# CIRCUIT_SCHEMATIC.net
KiCad netlist of a schematic drawn in EAGLE
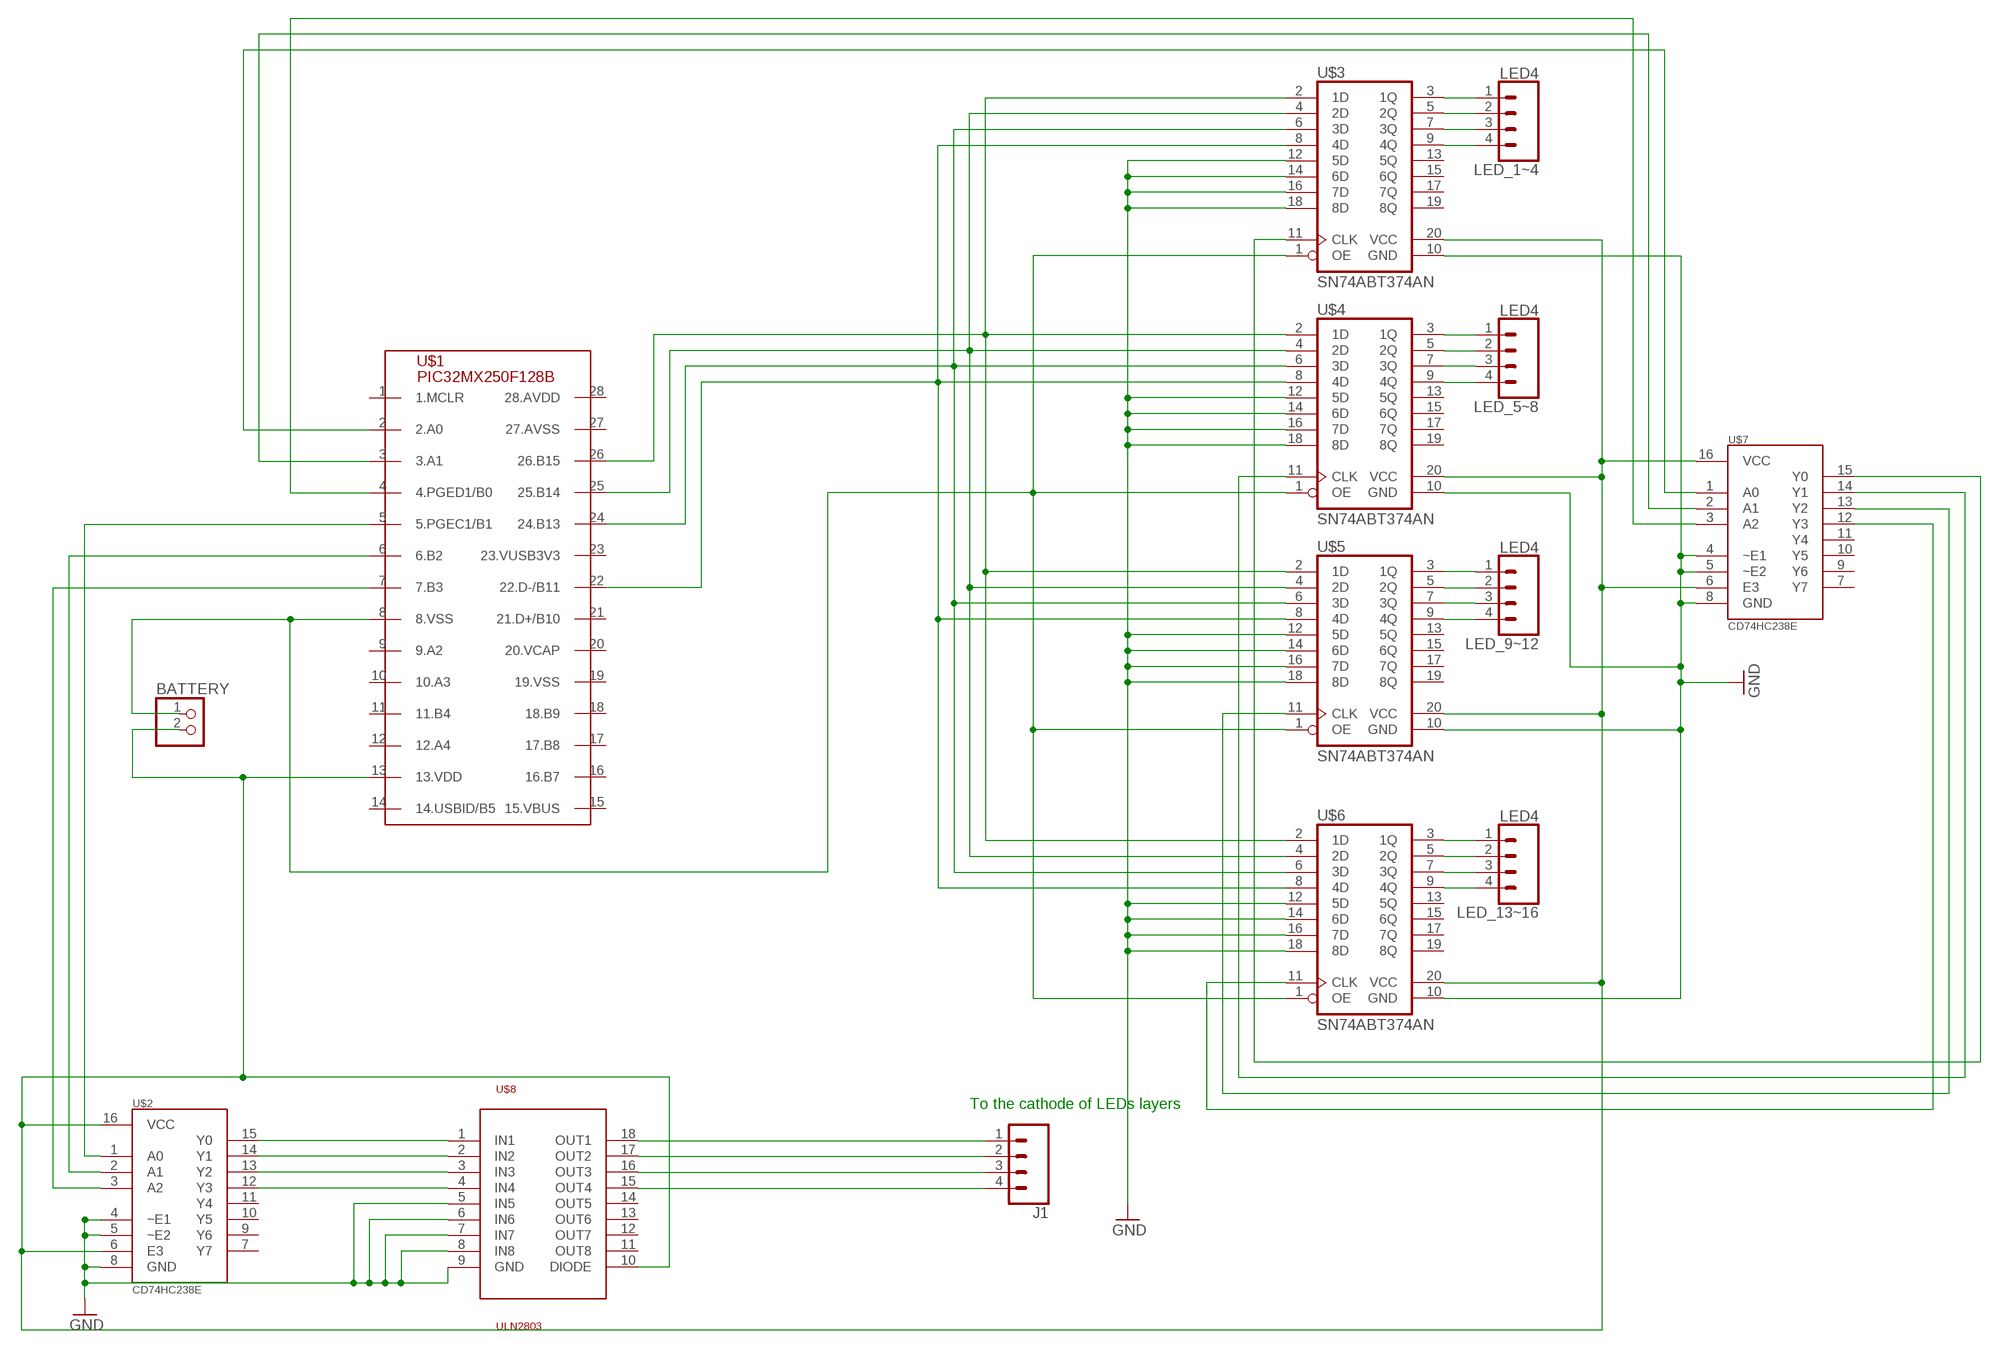
[diagram p0: schematic, sheet 1]

(export (version "E")
  (design (tool "Eeschema 10.0.6"))
  (components
    (comp (ref "BATTERY")
      (value "PINHD-1X2")
      (footprint "eagle-import:1X02")
      (libsource (lib "eagle-import") (part "PINHD-1X2"))
    )
    (comp (ref "J1")
      (value "CONN_04")
      (footprint "eagle-import:1X04")
      (libsource (lib "eagle-import") (part "CONN_04"))
    )
    (comp (ref "LED_1~4")
      (value "LED4")
      (footprint "eagle-import:1X04")
      (libsource (lib "eagle-import") (part "LED4"))
    )
    (comp (ref "LED_5~8")
      (value "LED4")
      (footprint "eagle-import:1X04")
      (libsource (lib "eagle-import") (part "LED4"))
    )
    (comp (ref "LED_9~12")
      (value "LED4")
      (footprint "eagle-import:1X04")
      (libsource (lib "eagle-import") (part "LED4"))
    )
    (comp (ref "LED_13~16")
      (value "LED4")
      (footprint "eagle-import:1X04")
      (libsource (lib "eagle-import") (part "LED4"))
    )
    (comp (ref "U$1")
      (value "PIC32MX250F128B")
      (footprint "eagle-import:DIL28-3")
      (libsource (lib "eagle-import") (part "PIC32MX250F128B"))
    )
    (comp (ref "U$2")
      (value "CD74HC238E")
      (footprint "eagle-import:DIL16")
      (libsource (lib "eagle-import") (part "CD74HC238E"))
    )
    (comp (ref "U$3")
      (value "SN74ABT374AN")
      (footprint "eagle-import:DIL20")
      (libsource (lib "eagle-import") (part "SN74ABT374AN"))
    )
    (comp (ref "U$4")
      (value "SN74ABT374AN")
      (footprint "eagle-import:DIL20")
      (libsource (lib "eagle-import") (part "SN74ABT374AN"))
    )
    (comp (ref "U$5")
      (value "SN74ABT374AN")
      (footprint "eagle-import:DIL20")
      (libsource (lib "eagle-import") (part "SN74ABT374AN"))
    )
    (comp (ref "U$6")
      (value "SN74ABT374AN")
      (footprint "eagle-import:DIL20")
      (libsource (lib "eagle-import") (part "SN74ABT374AN"))
    )
    (comp (ref "U$7")
      (value "CD74HC238E")
      (footprint "eagle-import:DIL16")
      (libsource (lib "eagle-import") (part "CD74HC238E"))
    )
    (comp (ref "U$8")
      (value "ULN2803")
      (footprint "eagle-import:SO18L")
      (libsource (lib "eagle-import") (part "ULN2803"))
    )
  )
  (nets
    (net (code "1") (name "GND") (class "Default")
      (node (ref "U$2") (pin "4") (pinfunction "~{E1}_4") (pintype "bidirectional"))
      (node (ref "U$2") (pin "5") (pinfunction "~{E2}_5") (pintype "bidirectional"))
      (node (ref "U$2") (pin "8") (pinfunction "GND_8") (pintype "bidirectional"))
      (node (ref "U$3") (pin "10") (pinfunction "GND_10") (pintype "bidirectional"))
      (node (ref "U$3") (pin "12") (pinfunction "5D_12") (pintype "input"))
      (node (ref "U$3") (pin "14") (pinfunction "6D_14") (pintype "input"))
      (node (ref "U$3") (pin "16") (pinfunction "7D_16") (pintype "input"))
      (node (ref "U$3") (pin "18") (pinfunction "8D_18") (pintype "input"))
      (node (ref "U$4") (pin "10") (pinfunction "GND_10") (pintype "bidirectional"))
      (node (ref "U$4") (pin "12") (pinfunction "5D_12") (pintype "input"))
      (node (ref "U$4") (pin "14") (pinfunction "6D_14") (pintype "input"))
      (node (ref "U$4") (pin "16") (pinfunction "7D_16") (pintype "input"))
      (node (ref "U$4") (pin "18") (pinfunction "8D_18") (pintype "input"))
      (node (ref "U$5") (pin "10") (pinfunction "GND_10") (pintype "bidirectional"))
      (node (ref "U$5") (pin "12") (pinfunction "5D_12") (pintype "input"))
      (node (ref "U$5") (pin "14") (pinfunction "6D_14") (pintype "input"))
      (node (ref "U$5") (pin "16") (pinfunction "7D_16") (pintype "input"))
      (node (ref "U$5") (pin "18") (pinfunction "8D_18") (pintype "input"))
      (node (ref "U$6") (pin "10") (pinfunction "GND_10") (pintype "bidirectional"))
      (node (ref "U$6") (pin "12") (pinfunction "5D_12") (pintype "input"))
      (node (ref "U$6") (pin "14") (pinfunction "6D_14") (pintype "input"))
      (node (ref "U$6") (pin "16") (pinfunction "7D_16") (pintype "input"))
      (node (ref "U$6") (pin "18") (pinfunction "8D_18") (pintype "input"))
      (node (ref "U$7") (pin "4") (pinfunction "~{E1}_4") (pintype "bidirectional"))
      (node (ref "U$7") (pin "5") (pinfunction "~{E2}_5") (pintype "bidirectional"))
      (node (ref "U$7") (pin "8") (pinfunction "GND_8") (pintype "bidirectional"))
      (node (ref "U$8") (pin "5") (pinfunction "IN5_5") (pintype "input"))
      (node (ref "U$8") (pin "6") (pinfunction "IN6_6") (pintype "input"))
      (node (ref "U$8") (pin "7") (pinfunction "IN7_7") (pintype "input"))
      (node (ref "U$8") (pin "8") (pinfunction "IN8_8") (pintype "input"))
      (node (ref "U$8") (pin "9") (pinfunction "GND_9") (pintype "power_in"))
    )
    (net (code "2") (name "Net-(U$1-2.A0)") (class "Default")
      (node (ref "U$1") (pin "2") (pinfunction "2.A0_2") (pintype "bidirectional"))
      (node (ref "U$7") (pin "1") (pinfunction "A0_1") (pintype "bidirectional"))
    )
    (net (code "3") (name "Net-(U$1-3.A1)") (class "Default")
      (node (ref "U$1") (pin "3") (pinfunction "3.A1_3") (pintype "bidirectional"))
      (node (ref "U$7") (pin "2") (pinfunction "A1_2") (pintype "bidirectional"))
    )
    (net (code "4") (name "Net-(U$1-4.PGED1{slash}B0)") (class "Default")
      (node (ref "U$1") (pin "4") (pinfunction "4.PGED1/B0_4") (pintype "bidirectional"))
      (node (ref "U$7") (pin "3") (pinfunction "A2_3") (pintype "bidirectional"))
    )
    (net (code "5") (name "Net-(U$1-5.PGEC1{slash}B1)") (class "Default")
      (node (ref "U$1") (pin "5") (pinfunction "5.PGEC1/B1_5") (pintype "bidirectional"))
      (node (ref "U$2") (pin "1") (pinfunction "A0_1") (pintype "bidirectional"))
    )
    (net (code "6") (name "Net-(U$1-6.B2)") (class "Default")
      (node (ref "U$1") (pin "6") (pinfunction "6.B2_6") (pintype "bidirectional"))
      (node (ref "U$2") (pin "2") (pinfunction "A1_2") (pintype "bidirectional"))
    )
    (net (code "7") (name "Net-(U$1-7.B3)") (class "Default")
      (node (ref "U$1") (pin "7") (pinfunction "7.B3_7") (pintype "bidirectional"))
      (node (ref "U$2") (pin "3") (pinfunction "A2_3") (pintype "bidirectional"))
    )
    (net (code "8") (name "Net-(U$1-8.VSS)") (class "Default")
      (node (ref "BATTERY") (pin "1") (pinfunction "1_1") (pintype "passive"))
      (node (ref "U$1") (pin "8") (pinfunction "8.VSS_8") (pintype "bidirectional"))
      (node (ref "U$3") (pin "1") (pinfunction "OE_1") (pintype "input"))
      (node (ref "U$4") (pin "1") (pinfunction "OE_1") (pintype "input"))
      (node (ref "U$5") (pin "1") (pinfunction "OE_1") (pintype "input"))
      (node (ref "U$6") (pin "1") (pinfunction "OE_1") (pintype "input"))
    )
    (net (code "9") (name "Net-(U$1-13.VDD)") (class "Default")
      (node (ref "BATTERY") (pin "2") (pinfunction "2_2") (pintype "passive"))
      (node (ref "U$1") (pin "13") (pinfunction "13.VDD_13") (pintype "bidirectional"))
      (node (ref "U$2") (pin "16") (pinfunction "VCC_16") (pintype "bidirectional"))
      (node (ref "U$2") (pin "6") (pinfunction "E3_6") (pintype "bidirectional"))
      (node (ref "U$3") (pin "20") (pinfunction "VCC_20") (pintype "bidirectional"))
      (node (ref "U$4") (pin "20") (pinfunction "VCC_20") (pintype "bidirectional"))
      (node (ref "U$5") (pin "20") (pinfunction "VCC_20") (pintype "bidirectional"))
      (node (ref "U$6") (pin "20") (pinfunction "VCC_20") (pintype "bidirectional"))
      (node (ref "U$7") (pin "16") (pinfunction "VCC_16") (pintype "bidirectional"))
      (node (ref "U$7") (pin "6") (pinfunction "E3_6") (pintype "bidirectional"))
      (node (ref "U$8") (pin "10") (pinfunction "DIODE_10") (pintype "power_in"))
    )
    (net (code "10") (name "Net-(U$1-22.D-{slash}B11)") (class "Default")
      (node (ref "U$1") (pin "22") (pinfunction "22.D-/B11_22") (pintype "bidirectional"))
      (node (ref "U$3") (pin "8") (pinfunction "4D_8") (pintype "input"))
      (node (ref "U$4") (pin "8") (pinfunction "4D_8") (pintype "input"))
      (node (ref "U$5") (pin "8") (pinfunction "4D_8") (pintype "input"))
      (node (ref "U$6") (pin "8") (pinfunction "4D_8") (pintype "input"))
    )
    (net (code "11") (name "Net-(U$1-24.B13)") (class "Default")
      (node (ref "U$1") (pin "24") (pinfunction "24.B13_24") (pintype "bidirectional"))
      (node (ref "U$3") (pin "6") (pinfunction "3D_6") (pintype "input"))
      (node (ref "U$4") (pin "6") (pinfunction "3D_6") (pintype "input"))
      (node (ref "U$5") (pin "6") (pinfunction "3D_6") (pintype "input"))
      (node (ref "U$6") (pin "6") (pinfunction "3D_6") (pintype "input"))
    )
    (net (code "12") (name "Net-(U$1-25.B14)") (class "Default")
      (node (ref "U$1") (pin "25") (pinfunction "25.B14_25") (pintype "bidirectional"))
      (node (ref "U$3") (pin "4") (pinfunction "2D_4") (pintype "input"))
      (node (ref "U$4") (pin "4") (pinfunction "2D_4") (pintype "input"))
      (node (ref "U$5") (pin "4") (pinfunction "2D_4") (pintype "input"))
      (node (ref "U$6") (pin "4") (pinfunction "2D_4") (pintype "input"))
    )
    (net (code "13") (name "Net-(U$1-26.B15)") (class "Default")
      (node (ref "U$1") (pin "26") (pinfunction "26.B15_26") (pintype "bidirectional"))
      (node (ref "U$3") (pin "2") (pinfunction "1D_2") (pintype "input"))
      (node (ref "U$4") (pin "2") (pinfunction "1D_2") (pintype "input"))
      (node (ref "U$5") (pin "2") (pinfunction "1D_2") (pintype "input"))
      (node (ref "U$6") (pin "2") (pinfunction "1D_2") (pintype "input"))
    )
    (net (code "14") (name "Net-(U$2-Y0)") (class "Default")
      (node (ref "U$2") (pin "15") (pinfunction "Y0_15") (pintype "bidirectional"))
      (node (ref "U$8") (pin "1") (pinfunction "IN1_1") (pintype "input"))
    )
    (net (code "15") (name "Net-(U$2-Y1)") (class "Default")
      (node (ref "U$2") (pin "14") (pinfunction "Y1_14") (pintype "bidirectional"))
      (node (ref "U$8") (pin "2") (pinfunction "IN2_2") (pintype "input"))
    )
    (net (code "16") (name "Net-(U$2-Y2)") (class "Default")
      (node (ref "U$2") (pin "13") (pinfunction "Y2_13") (pintype "bidirectional"))
      (node (ref "U$8") (pin "3") (pinfunction "IN3_3") (pintype "input"))
    )
    (net (code "17") (name "Net-(U$2-Y3)") (class "Default")
      (node (ref "U$2") (pin "12") (pinfunction "Y3_12") (pintype "bidirectional"))
      (node (ref "U$8") (pin "4") (pinfunction "IN4_4") (pintype "input"))
    )
    (net (code "18") (name "Net-(U$3-1Q)") (class "Default")
      (node (ref "LED_1~4") (pin "1") (pinfunction "1_1") (pintype "passive"))
      (node (ref "U$3") (pin "3") (pinfunction "1Q_3") (pintype "tri_state"))
    )
    (net (code "19") (name "Net-(U$3-2Q)") (class "Default")
      (node (ref "LED_1~4") (pin "2") (pinfunction "2_2") (pintype "passive"))
      (node (ref "U$3") (pin "5") (pinfunction "2Q_5") (pintype "tri_state"))
    )
    (net (code "20") (name "Net-(U$3-3Q)") (class "Default")
      (node (ref "LED_1~4") (pin "3") (pinfunction "3_3") (pintype "passive"))
      (node (ref "U$3") (pin "7") (pinfunction "3Q_7") (pintype "tri_state"))
    )
    (net (code "21") (name "Net-(U$3-4Q)") (class "Default")
      (node (ref "LED_1~4") (pin "4") (pinfunction "4_4") (pintype "passive"))
      (node (ref "U$3") (pin "9") (pinfunction "4Q_9") (pintype "tri_state"))
    )
    (net (code "22") (name "Net-(U$3-CLK)") (class "Default")
      (node (ref "U$3") (pin "11") (pinfunction "CLK_11") (pintype "input"))
      (node (ref "U$7") (pin "15") (pinfunction "Y0_15") (pintype "bidirectional"))
    )
    (net (code "23") (name "Net-(U$4-1Q)") (class "Default")
      (node (ref "LED_5~8") (pin "1") (pinfunction "1_1") (pintype "passive"))
      (node (ref "U$4") (pin "3") (pinfunction "1Q_3") (pintype "tri_state"))
    )
    (net (code "24") (name "Net-(U$4-2Q)") (class "Default")
      (node (ref "LED_5~8") (pin "2") (pinfunction "2_2") (pintype "passive"))
      (node (ref "U$4") (pin "5") (pinfunction "2Q_5") (pintype "tri_state"))
    )
    (net (code "25") (name "Net-(U$4-3Q)") (class "Default")
      (node (ref "LED_5~8") (pin "3") (pinfunction "3_3") (pintype "passive"))
      (node (ref "U$4") (pin "7") (pinfunction "3Q_7") (pintype "tri_state"))
    )
    (net (code "26") (name "Net-(U$4-4Q)") (class "Default")
      (node (ref "LED_5~8") (pin "4") (pinfunction "4_4") (pintype "passive"))
      (node (ref "U$4") (pin "9") (pinfunction "4Q_9") (pintype "tri_state"))
    )
    (net (code "27") (name "Net-(U$4-CLK)") (class "Default")
      (node (ref "U$4") (pin "11") (pinfunction "CLK_11") (pintype "input"))
      (node (ref "U$7") (pin "14") (pinfunction "Y1_14") (pintype "bidirectional"))
    )
    (net (code "28") (name "Net-(U$5-1Q)") (class "Default")
      (node (ref "LED_9~12") (pin "1") (pinfunction "1_1") (pintype "passive"))
      (node (ref "U$5") (pin "3") (pinfunction "1Q_3") (pintype "tri_state"))
    )
    (net (code "29") (name "Net-(U$5-2Q)") (class "Default")
      (node (ref "LED_9~12") (pin "2") (pinfunction "2_2") (pintype "passive"))
      (node (ref "U$5") (pin "5") (pinfunction "2Q_5") (pintype "tri_state"))
    )
    (net (code "30") (name "Net-(U$5-3Q)") (class "Default")
      (node (ref "LED_9~12") (pin "3") (pinfunction "3_3") (pintype "passive"))
      (node (ref "U$5") (pin "7") (pinfunction "3Q_7") (pintype "tri_state"))
    )
    (net (code "31") (name "Net-(U$5-4Q)") (class "Default")
      (node (ref "LED_9~12") (pin "4") (pinfunction "4_4") (pintype "passive"))
      (node (ref "U$5") (pin "9") (pinfunction "4Q_9") (pintype "tri_state"))
    )
    (net (code "32") (name "Net-(U$5-CLK)") (class "Default")
      (node (ref "U$5") (pin "11") (pinfunction "CLK_11") (pintype "input"))
      (node (ref "U$7") (pin "13") (pinfunction "Y2_13") (pintype "bidirectional"))
    )
    (net (code "33") (name "Net-(U$6-1Q)") (class "Default")
      (node (ref "LED_13~16") (pin "1") (pinfunction "1_1") (pintype "passive"))
      (node (ref "U$6") (pin "3") (pinfunction "1Q_3") (pintype "tri_state"))
    )
    (net (code "34") (name "Net-(U$6-2Q)") (class "Default")
      (node (ref "LED_13~16") (pin "2") (pinfunction "2_2") (pintype "passive"))
      (node (ref "U$6") (pin "5") (pinfunction "2Q_5") (pintype "tri_state"))
    )
    (net (code "35") (name "Net-(U$6-3Q)") (class "Default")
      (node (ref "LED_13~16") (pin "3") (pinfunction "3_3") (pintype "passive"))
      (node (ref "U$6") (pin "7") (pinfunction "3Q_7") (pintype "tri_state"))
    )
    (net (code "36") (name "Net-(U$6-4Q)") (class "Default")
      (node (ref "LED_13~16") (pin "4") (pinfunction "4_4") (pintype "passive"))
      (node (ref "U$6") (pin "9") (pinfunction "4Q_9") (pintype "tri_state"))
    )
    (net (code "37") (name "Net-(U$6-CLK)") (class "Default")
      (node (ref "U$6") (pin "11") (pinfunction "CLK_11") (pintype "input"))
      (node (ref "U$7") (pin "12") (pinfunction "Y3_12") (pintype "bidirectional"))
    )
    (net (code "38") (name "Net-(U$8-OUT1)") (class "Default")
      (node (ref "J1") (pin "1") (pinfunction "1_1") (pintype "passive"))
      (node (ref "U$8") (pin "18") (pinfunction "OUT1_18") (pintype "open_collector"))
    )
    (net (code "39") (name "Net-(U$8-OUT2)") (class "Default")
      (node (ref "J1") (pin "2") (pinfunction "2_2") (pintype "passive"))
      (node (ref "U$8") (pin "17") (pinfunction "OUT2_17") (pintype "open_collector"))
    )
    (net (code "40") (name "Net-(U$8-OUT3)") (class "Default")
      (node (ref "J1") (pin "3") (pinfunction "3_3") (pintype "passive"))
      (node (ref "U$8") (pin "16") (pinfunction "OUT3_16") (pintype "open_collector"))
    )
    (net (code "41") (name "Net-(U$8-OUT4)") (class "Default")
      (node (ref "J1") (pin "4") (pinfunction "4_4") (pintype "passive"))
      (node (ref "U$8") (pin "15") (pinfunction "OUT4_15") (pintype "open_collector"))
    )
    (net (code "42") (name "unconnected-(U$1-1.MCLR-Pad1)") (class "Default")
      (node (ref "U$1") (pin "1") (pinfunction "1.MCLR_1") (pintype "bidirectional"))
    )
    (net (code "43") (name "unconnected-(U$1-9.A2-Pad9)") (class "Default")
      (node (ref "U$1") (pin "9") (pinfunction "9.A2_9") (pintype "bidirectional"))
    )
    (net (code "44") (name "unconnected-(U$1-10.A3-Pad10)") (class "Default")
      (node (ref "U$1") (pin "10") (pinfunction "10.A3_10") (pintype "bidirectional"))
    )
    (net (code "45") (name "unconnected-(U$1-11.B4-Pad11)") (class "Default")
      (node (ref "U$1") (pin "11") (pinfunction "11.B4_11") (pintype "bidirectional"))
    )
    (net (code "46") (name "unconnected-(U$1-12.A4-Pad12)") (class "Default")
      (node (ref "U$1") (pin "12") (pinfunction "12.A4_12") (pintype "bidirectional"))
    )
    (net (code "47") (name "unconnected-(U$1-14.USBID{slash}B5-Pad14)") (class "Default")
      (node (ref "U$1") (pin "14") (pinfunction "14.USBID/B5_14") (pintype "bidirectional"))
    )
    (net (code "48") (name "unconnected-(U$1-15.VBUS-Pad15)") (class "Default")
      (node (ref "U$1") (pin "15") (pinfunction "15.VBUS_15") (pintype "bidirectional"))
    )
    (net (code "49") (name "unconnected-(U$1-16.B7-Pad16)") (class "Default")
      (node (ref "U$1") (pin "16") (pinfunction "16.B7_16") (pintype "bidirectional"))
    )
    (net (code "50") (name "unconnected-(U$1-17.B8-Pad17)") (class "Default")
      (node (ref "U$1") (pin "17") (pinfunction "17.B8_17") (pintype "bidirectional"))
    )
    (net (code "51") (name "unconnected-(U$1-18.B9-Pad18)") (class "Default")
      (node (ref "U$1") (pin "18") (pinfunction "18.B9_18") (pintype "bidirectional"))
    )
    (net (code "52") (name "unconnected-(U$1-19.VSS-Pad19)") (class "Default")
      (node (ref "U$1") (pin "19") (pinfunction "19.VSS_19") (pintype "bidirectional"))
    )
    (net (code "53") (name "unconnected-(U$1-20.VCAP-Pad20)") (class "Default")
      (node (ref "U$1") (pin "20") (pinfunction "20.VCAP_20") (pintype "bidirectional"))
    )
    (net (code "54") (name "unconnected-(U$1-21.D+{slash}B10-Pad21)") (class "Default")
      (node (ref "U$1") (pin "21") (pinfunction "21.D+/B10_21") (pintype "bidirectional"))
    )
    (net (code "55") (name "unconnected-(U$1-23.VUSB3V3-Pad23)") (class "Default")
      (node (ref "U$1") (pin "23") (pinfunction "23.VUSB3V3_23") (pintype "bidirectional"))
    )
    (net (code "56") (name "unconnected-(U$1-27.AVSS-Pad27)") (class "Default")
      (node (ref "U$1") (pin "27") (pinfunction "27.AVSS_27") (pintype "bidirectional"))
    )
    (net (code "57") (name "unconnected-(U$1-28.AVDD-Pad28)") (class "Default")
      (node (ref "U$1") (pin "28") (pinfunction "28.AVDD_28") (pintype "bidirectional"))
    )
    (net (code "58") (name "unconnected-(U$2-Y4-Pad11)") (class "Default")
      (node (ref "U$2") (pin "11") (pinfunction "Y4_11") (pintype "bidirectional"))
    )
    (net (code "59") (name "unconnected-(U$2-Y5-Pad10)") (class "Default")
      (node (ref "U$2") (pin "10") (pinfunction "Y5_10") (pintype "bidirectional"))
    )
    (net (code "60") (name "unconnected-(U$2-Y6-Pad9)") (class "Default")
      (node (ref "U$2") (pin "9") (pinfunction "Y6_9") (pintype "bidirectional"))
    )
    (net (code "61") (name "unconnected-(U$2-Y7-Pad7)") (class "Default")
      (node (ref "U$2") (pin "7") (pinfunction "Y7_7") (pintype "bidirectional"))
    )
    (net (code "62") (name "unconnected-(U$3-5Q-Pad13)") (class "Default")
      (node (ref "U$3") (pin "13") (pinfunction "5Q_13") (pintype "tri_state"))
    )
    (net (code "63") (name "unconnected-(U$3-6Q-Pad15)") (class "Default")
      (node (ref "U$3") (pin "15") (pinfunction "6Q_15") (pintype "tri_state"))
    )
    (net (code "64") (name "unconnected-(U$3-7Q-Pad17)") (class "Default")
      (node (ref "U$3") (pin "17") (pinfunction "7Q_17") (pintype "tri_state"))
    )
    (net (code "65") (name "unconnected-(U$3-8Q-Pad19)") (class "Default")
      (node (ref "U$3") (pin "19") (pinfunction "8Q_19") (pintype "tri_state"))
    )
    (net (code "66") (name "unconnected-(U$4-5Q-Pad13)") (class "Default")
      (node (ref "U$4") (pin "13") (pinfunction "5Q_13") (pintype "tri_state"))
    )
    (net (code "67") (name "unconnected-(U$4-6Q-Pad15)") (class "Default")
      (node (ref "U$4") (pin "15") (pinfunction "6Q_15") (pintype "tri_state"))
    )
    (net (code "68") (name "unconnected-(U$4-7Q-Pad17)") (class "Default")
      (node (ref "U$4") (pin "17") (pinfunction "7Q_17") (pintype "tri_state"))
    )
    (net (code "69") (name "unconnected-(U$4-8Q-Pad19)") (class "Default")
      (node (ref "U$4") (pin "19") (pinfunction "8Q_19") (pintype "tri_state"))
    )
    (net (code "70") (name "unconnected-(U$5-5Q-Pad13)") (class "Default")
      (node (ref "U$5") (pin "13") (pinfunction "5Q_13") (pintype "tri_state"))
    )
    (net (code "71") (name "unconnected-(U$5-6Q-Pad15)") (class "Default")
      (node (ref "U$5") (pin "15") (pinfunction "6Q_15") (pintype "tri_state"))
    )
    (net (code "72") (name "unconnected-(U$5-7Q-Pad17)") (class "Default")
      (node (ref "U$5") (pin "17") (pinfunction "7Q_17") (pintype "tri_state"))
    )
    (net (code "73") (name "unconnected-(U$5-8Q-Pad19)") (class "Default")
      (node (ref "U$5") (pin "19") (pinfunction "8Q_19") (pintype "tri_state"))
    )
    (net (code "74") (name "unconnected-(U$6-5Q-Pad13)") (class "Default")
      (node (ref "U$6") (pin "13") (pinfunction "5Q_13") (pintype "tri_state"))
    )
    (net (code "75") (name "unconnected-(U$6-6Q-Pad15)") (class "Default")
      (node (ref "U$6") (pin "15") (pinfunction "6Q_15") (pintype "tri_state"))
    )
    (net (code "76") (name "unconnected-(U$6-7Q-Pad17)") (class "Default")
      (node (ref "U$6") (pin "17") (pinfunction "7Q_17") (pintype "tri_state"))
    )
    (net (code "77") (name "unconnected-(U$6-8Q-Pad19)") (class "Default")
      (node (ref "U$6") (pin "19") (pinfunction "8Q_19") (pintype "tri_state"))
    )
    (net (code "78") (name "unconnected-(U$7-Y4-Pad11)") (class "Default")
      (node (ref "U$7") (pin "11") (pinfunction "Y4_11") (pintype "bidirectional"))
    )
    (net (code "79") (name "unconnected-(U$7-Y5-Pad10)") (class "Default")
      (node (ref "U$7") (pin "10") (pinfunction "Y5_10") (pintype "bidirectional"))
    )
    (net (code "80") (name "unconnected-(U$7-Y6-Pad9)") (class "Default")
      (node (ref "U$7") (pin "9") (pinfunction "Y6_9") (pintype "bidirectional"))
    )
    (net (code "81") (name "unconnected-(U$7-Y7-Pad7)") (class "Default")
      (node (ref "U$7") (pin "7") (pinfunction "Y7_7") (pintype "bidirectional"))
    )
    (net (code "82") (name "unconnected-(U$8-OUT5-Pad14)") (class "Default")
      (node (ref "U$8") (pin "14") (pinfunction "OUT5_14") (pintype "open_collector"))
    )
    (net (code "83") (name "unconnected-(U$8-OUT6-Pad13)") (class "Default")
      (node (ref "U$8") (pin "13") (pinfunction "OUT6_13") (pintype "open_collector"))
    )
    (net (code "84") (name "unconnected-(U$8-OUT7-Pad12)") (class "Default")
      (node (ref "U$8") (pin "12") (pinfunction "OUT7_12") (pintype "open_collector"))
    )
    (net (code "85") (name "unconnected-(U$8-OUT8-Pad11)") (class "Default")
      (node (ref "U$8") (pin "11") (pinfunction "OUT8_11") (pintype "open_collector"))
    )
  )
)
